# arduinoboardwithphotoresistors4-WillUpda.net
KiCad netlist of a schematic drawn in EAGLE
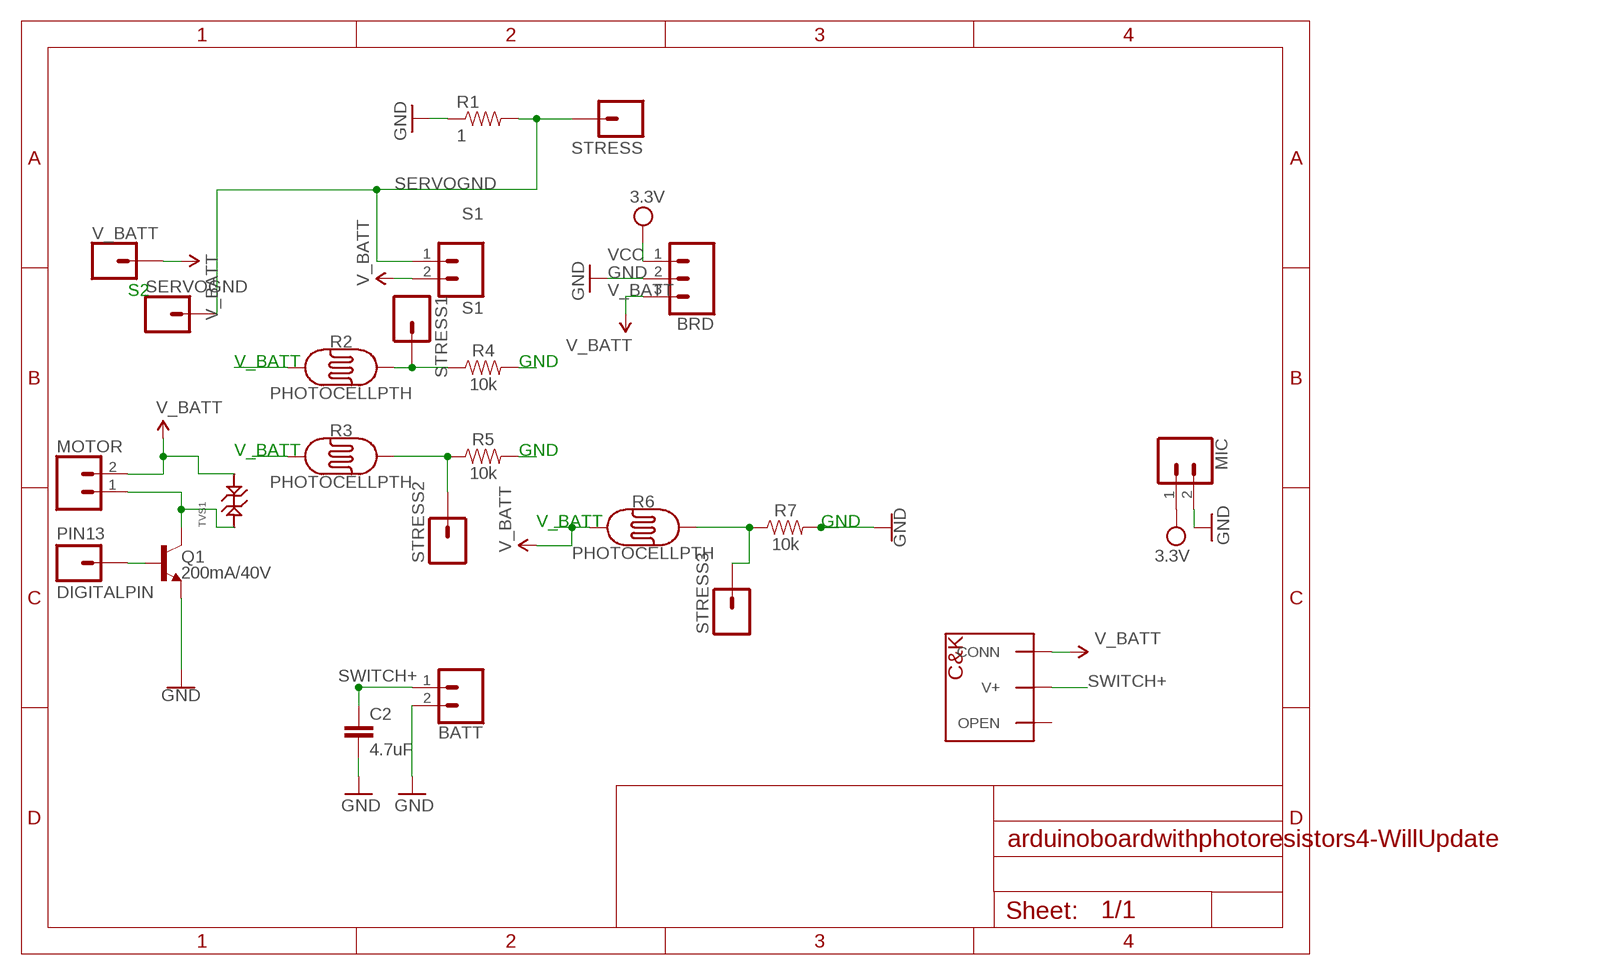
[diagram p0: schematic, sheet 1]

(export (version "E")
  (design (tool "Eeschema 10.0.6"))
  (components
    (comp (ref "BATT")
      (value "CONN_02")
      (footprint "eagle-import:1X02")
      (libsource (lib "eagle-import") (part "CONN_02"))
    )
    (comp (ref "BRD")
      (value "CONN_03")
      (footprint "eagle-import:1X03")
      (libsource (lib "eagle-import") (part "CONN_03"))
    )
    (comp (ref "C2")
      (value "4.7uF")
      (footprint "eagle-import:0603-CAP")
      (libsource (lib "eagle-import") (part "4.7UF-6.3V-10%(0603)0603"))
    )
    (comp (ref "MIC")
      (value "CONN_02")
      (footprint "eagle-import:1X02")
      (libsource (lib "eagle-import") (part "CONN_02"))
    )
    (comp (ref "MOTOR")
      (value "CONN_02")
      (footprint "eagle-import:1X02")
      (libsource (lib "eagle-import") (part "CONN_02"))
    )
    (comp (ref "PIN13")
      (value "DIGITALPIN")
      (footprint "eagle-import:1X01")
      (libsource (lib "eagle-import") (part "M01PTH"))
    )
    (comp (ref "Q1")
      (value "200mA/40V")
      (footprint "eagle-import:TO-92")
      (libsource (lib "eagle-import") (part "TRANS_NPN-2N3904"))
    )
    (comp (ref "R1")
      (value "1")
      (footprint "eagle-import:0603-RES")
      (libsource (lib "eagle-import") (part "2.0KOHM1/10W5%(0603)"))
    )
    (comp (ref "R2")
      (value "PHOTOCELLPTH")
      (footprint "eagle-import:PHOTOCELL")
      (libsource (lib "eagle-import") (part "PHOTOCELLPTH"))
    )
    (comp (ref "R3")
      (value "PHOTOCELLPTH")
      (footprint "eagle-import:PHOTOCELL")
      (libsource (lib "eagle-import") (part "PHOTOCELLPTH"))
    )
    (comp (ref "R4")
      (value "10k")
      (footprint "eagle-import:0603")
      (libsource (lib "eagle-import") (part "10KOHM-0603-1/10W-1%"))
    )
    (comp (ref "R5")
      (value "10k")
      (footprint "eagle-import:0603")
      (libsource (lib "eagle-import") (part "10KOHM-0603-1/10W-1%"))
    )
    (comp (ref "R6")
      (value "PHOTOCELLPTH")
      (footprint "eagle-import:PHOTOCELL")
      (libsource (lib "eagle-import") (part "PHOTOCELLPTH"))
    )
    (comp (ref "R7")
      (value "10k")
      (footprint "eagle-import:0603")
      (libsource (lib "eagle-import") (part "10KOHM-0603-1/10W-1%"))
    )
    (comp (ref "S1")
      (value "S1")
      (footprint "eagle-import:1X02")
      (libsource (lib "eagle-import") (part "CONN_02"))
    )
    (comp (ref "SERVOGND")
      (value "CONN_01")
      (footprint "eagle-import:1X01")
      (libsource (lib "eagle-import") (part "CONN_01"))
    )
    (comp (ref "STRESS")
      (value "M01PTH")
      (footprint "eagle-import:1X01")
      (libsource (lib "eagle-import") (part "M01PTH"))
    )
    (comp (ref "STRESS1")
      (value "M01PTH")
      (footprint "eagle-import:1X01")
      (libsource (lib "eagle-import") (part "M01PTH"))
    )
    (comp (ref "STRESS2")
      (value "M01PTH")
      (footprint "eagle-import:1X01")
      (libsource (lib "eagle-import") (part "M01PTH"))
    )
    (comp (ref "STRESS3")
      (value "M01PTH")
      (footprint "eagle-import:1X01")
      (libsource (lib "eagle-import") (part "M01PTH"))
    )
    (comp (ref "TVS1")
      (value "TVS_DIODE_SOD-923")
      (footprint "eagle-import:SOD-923")
      (libsource (lib "eagle-import") (part "TVS_DIODE_SOD-923"))
    )
    (comp (ref "U$1")
      (value "WILL-BLACKSLIDESWITCH")
      (footprint "eagle-import:WILL-BLACKSLIDESWITCH")
      (libsource (lib "eagle-import") (part "WILL-BLACKSLIDESWITCH"))
    )
    (comp (ref "V_BATT")
      (value "CONN_01")
      (footprint "eagle-import:1X01")
      (libsource (lib "eagle-import") (part "CONN_01"))
    )
  )
  (nets
    (net (code "1") (name "/SERVOGND") (class "Default")
      (node (ref "R1") (pin "2") (pinfunction "2_2") (pintype "passive"))
      (node (ref "S1") (pin "1") (pinfunction "1_1") (pintype "passive"))
      (node (ref "SERVOGND") (pin "1") (pinfunction "1_1") (pintype "passive"))
      (node (ref "STRESS") (pin "1") (pinfunction "1_1") (pintype "passive"))
    )
    (net (code "2") (name "/SWITCH+") (class "Default")
      (node (ref "BATT") (pin "1") (pinfunction "1_1") (pintype "passive"))
      (node (ref "C2") (pin "1") (pinfunction "1_1") (pintype "passive"))
      (node (ref "U$1") (pin "V+") (pinfunction "V+_V+") (pintype "bidirectional"))
    )
    (net (code "3") (name "3.3V") (class "Default")
      (node (ref "BRD") (pin "1") (pinfunction "1_1") (pintype "passive"))
      (node (ref "MIC") (pin "1") (pinfunction "1_1") (pintype "passive"))
    )
    (net (code "4") (name "GND") (class "Default")
      (node (ref "BATT") (pin "2") (pinfunction "2_2") (pintype "passive"))
      (node (ref "BRD") (pin "2") (pinfunction "2_2") (pintype "passive"))
      (node (ref "C2") (pin "2") (pinfunction "2_2") (pintype "passive"))
      (node (ref "MIC") (pin "2") (pinfunction "2_2") (pintype "passive"))
      (node (ref "Q1") (pin "1") (pinfunction "E_1") (pintype "passive"))
      (node (ref "R1") (pin "1") (pinfunction "1_1") (pintype "passive"))
      (node (ref "R4") (pin "2") (pinfunction "2_2") (pintype "passive"))
      (node (ref "R5") (pin "2") (pinfunction "2_2") (pintype "passive"))
      (node (ref "R7") (pin "2") (pinfunction "2_2") (pintype "passive"))
    )
    (net (code "5") (name "Net-(Q1-B)") (class "Default")
      (node (ref "PIN13") (pin "1") (pinfunction "1_1") (pintype "passive"))
      (node (ref "Q1") (pin "2") (pinfunction "B_2") (pintype "passive"))
    )
    (net (code "6") (name "Net-(Q1-C)") (class "Default")
      (node (ref "MOTOR") (pin "1") (pinfunction "1_1") (pintype "passive"))
      (node (ref "Q1") (pin "3") (pinfunction "C_3") (pintype "passive"))
      (node (ref "TVS1") (pin "P$1") (pinfunction "P$1_P$1") (pintype "bidirectional"))
    )
    (net (code "7") (name "Net-(R2-P$2)") (class "Default")
      (node (ref "R2") (pin "2") (pinfunction "P$2_2") (pintype "bidirectional"))
      (node (ref "R4") (pin "1") (pinfunction "1_1") (pintype "passive"))
      (node (ref "STRESS1") (pin "1") (pinfunction "1_1") (pintype "passive"))
    )
    (net (code "8") (name "Net-(R3-P$2)") (class "Default")
      (node (ref "R3") (pin "2") (pinfunction "P$2_2") (pintype "bidirectional"))
      (node (ref "R5") (pin "1") (pinfunction "1_1") (pintype "passive"))
      (node (ref "STRESS2") (pin "1") (pinfunction "1_1") (pintype "passive"))
    )
    (net (code "9") (name "Net-(R6-P$2)") (class "Default")
      (node (ref "R6") (pin "2") (pinfunction "P$2_2") (pintype "bidirectional"))
      (node (ref "R7") (pin "1") (pinfunction "1_1") (pintype "passive"))
      (node (ref "STRESS3") (pin "1") (pinfunction "1_1") (pintype "passive"))
    )
    (net (code "10") (name "V_BATT") (class "Default")
      (node (ref "BRD") (pin "3") (pinfunction "3_3") (pintype "passive"))
      (node (ref "MOTOR") (pin "2") (pinfunction "2_2") (pintype "passive"))
      (node (ref "R2") (pin "1") (pinfunction "P$1_1") (pintype "bidirectional"))
      (node (ref "R3") (pin "1") (pinfunction "P$1_1") (pintype "bidirectional"))
      (node (ref "R6") (pin "1") (pinfunction "P$1_1") (pintype "bidirectional"))
      (node (ref "S1") (pin "2") (pinfunction "2_2") (pintype "passive"))
      (node (ref "TVS1") (pin "P$2") (pinfunction "P$2_P$2") (pintype "bidirectional"))
      (node (ref "U$1") (pin "CONN") (pinfunction "CONN_CONN") (pintype "bidirectional"))
      (node (ref "V_BATT") (pin "1") (pinfunction "1_1") (pintype "passive"))
    )
    (net (code "11") (name "unconnected-(U$1-OPEN-PadNC)") (class "Default")
      (node (ref "U$1") (pin "NC") (pinfunction "OPEN_NC") (pintype "bidirectional"))
    )
  )
)
